# untitled.net
KiCad netlist of a schematic drawn in EAGLE
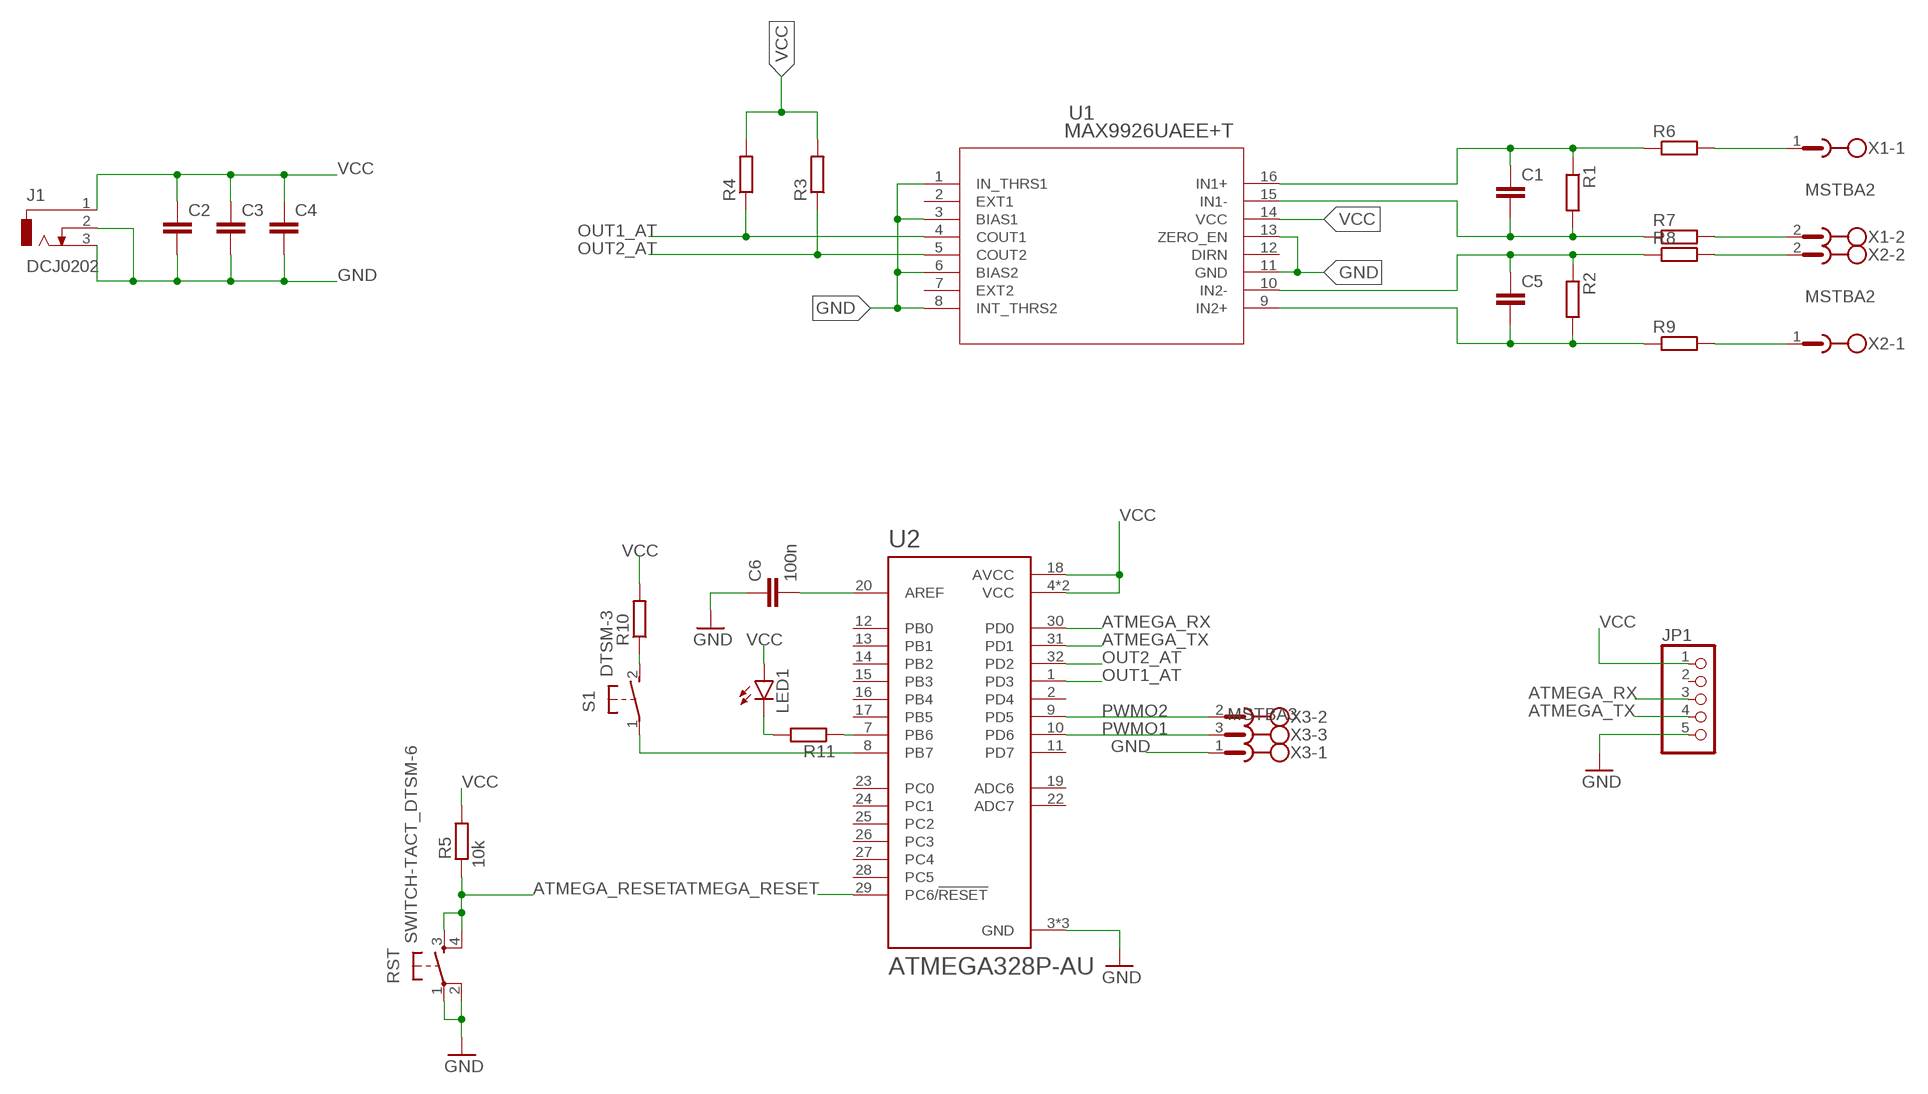
[diagram p0: schematic, sheet 1]

(export (version "E")
  (design (tool "Eeschema 10.0.6"))
  (components
    (comp (ref "C1")
      (value "C-EUC0805")
      (footprint "eagle-import:C0805")
      (libsource (lib "eagle-import") (part "C-EUC0805"))
    )
    (comp (ref "C2")
      (value "C-EUC0805")
      (footprint "eagle-import:C0805")
      (libsource (lib "eagle-import") (part "C-EUC0805"))
    )
    (comp (ref "C3")
      (value "C-EUC0805")
      (footprint "eagle-import:C0805")
      (libsource (lib "eagle-import") (part "C-EUC0805"))
    )
    (comp (ref "C4")
      (value "C-EUC0805")
      (footprint "eagle-import:C0805")
      (libsource (lib "eagle-import") (part "C-EUC0805"))
    )
    (comp (ref "C5")
      (value "C-EUC0805")
      (footprint "eagle-import:C0805")
      (libsource (lib "eagle-import") (part "C-EUC0805"))
    )
    (comp (ref "C6")
      (value "100n")
      (footprint "eagle-import:C0805")
      (libsource (lib "eagle-import") (part "C-EUC0805"))
    )
    (comp (ref "J1")
      (value "DCJ0202")
      (footprint "eagle-import:DCJ0202")
      (libsource (lib "eagle-import") (part "DCJ0202"))
    )
    (comp (ref "JP1")
      (value "PINHD-1X5")
      (footprint "eagle-import:1X05")
      (libsource (lib "eagle-import") (part "PINHD-1X5"))
    )
    (comp (ref "LED1")
      (value "LEDCHIP-LED0805")
      (footprint "eagle-import:CHIP-LED0805")
      (libsource (lib "eagle-import") (part "LEDCHIP-LED0805"))
    )
    (comp (ref "R1")
      (value "R-EU_R1206")
      (footprint "eagle-import:R1206")
      (libsource (lib "eagle-import") (part "R-EU_R1206"))
    )
    (comp (ref "R2")
      (value "R-EU_R1206")
      (footprint "eagle-import:R1206")
      (libsource (lib "eagle-import") (part "R-EU_R1206"))
    )
    (comp (ref "R3")
      (value "R-EU_R1206")
      (footprint "eagle-import:R1206")
      (libsource (lib "eagle-import") (part "R-EU_R1206"))
    )
    (comp (ref "R4")
      (value "R-EU_R1206")
      (footprint "eagle-import:R1206")
      (libsource (lib "eagle-import") (part "R-EU_R1206"))
    )
    (comp (ref "R5")
      (value "10k")
      (footprint "eagle-import:R1206")
      (libsource (lib "eagle-import") (part "R-EU_R1206"))
    )
    (comp (ref "R6")
      (value "R-EU_R2512")
      (footprint "eagle-import:R2512")
      (libsource (lib "eagle-import") (part "R-EU_R2512"))
    )
    (comp (ref "R7")
      (value "R-EU_R2512")
      (footprint "eagle-import:R2512")
      (libsource (lib "eagle-import") (part "R-EU_R2512"))
    )
    (comp (ref "R8")
      (value "R-EU_R2512")
      (footprint "eagle-import:R2512")
      (libsource (lib "eagle-import") (part "R-EU_R2512"))
    )
    (comp (ref "R9")
      (value "R-EU_R2512")
      (footprint "eagle-import:R2512")
      (libsource (lib "eagle-import") (part "R-EU_R2512"))
    )
    (comp (ref "R10")
      (value "R-EU_R1206")
      (footprint "eagle-import:R1206")
      (libsource (lib "eagle-import") (part "R-EU_R1206"))
    )
    (comp (ref "R11")
      (value "R-EU_R1206")
      (footprint "eagle-import:R1206")
      (libsource (lib "eagle-import") (part "R-EU_R1206"))
    )
    (comp (ref "RST")
      (value "SWITCH-TACT_DTSM-6")
      (footprint "eagle-import:SWITCH-TACT_DTSM-6")
      (libsource (lib "eagle-import") (part "SWITCH-TACT_DTSM-6"))
    )
    (comp (ref "S1")
      (value "DTSM-3")
      (footprint "eagle-import:DTSM-3")
      (libsource (lib "eagle-import") (part "DTSM-3"))
    )
    (comp (ref "U1")
      (value "MAX9926UAEE+T")
      (footprint "eagle-import:21-0055H_16_MXM")
      (fields (field (name "COPYRIGHT") "Copyright (C) 2018 Accelerated Designs. All rights reserved"))
      (libsource (lib "eagle-import") (part "MAX9926UAEE+T"))
    )
    (comp (ref "U2")
      (value "ATMEGA328P-AU")
      (footprint "eagle-import:QFP80P900X900X120-32N")
      (fields (field (name "MF") "Microchip Technology"))
      (libsource (lib "eagle-import") (part "ATMEGA328P-AU"))
    )
    (comp (ref "X1")
      (value "MSTBA2")
      (footprint "eagle-import:MSTBA2")
      (fields (field (name "MF") "FARNELL") (field (name "MPN") "1757242"))
      (libsource (lib "eagle-import") (part "MSTBA2"))
    )
    (comp (ref "X2")
      (value "MSTBA2")
      (footprint "eagle-import:MSTBA2")
      (fields (field (name "MF") "FARNELL") (field (name "MPN") "1757242"))
      (libsource (lib "eagle-import") (part "MSTBA2"))
    )
    (comp (ref "X3")
      (value "MSTBA3")
      (footprint "eagle-import:MSTBA3")
      (fields (field (name "MF") "FARNELL") (field (name "MPN") "1757255"))
      (libsource (lib "eagle-import") (part "MSTBA3"))
    )
  )
  (nets
    (net (code "1") (name "/ATMEGA_RESET") (class "Default")
      (node (ref "R5") (pin "1") (pinfunction "1_1") (pintype "passive"))
      (node (ref "RST") (pin "3") (pinfunction "3_3") (pintype "passive"))
      (node (ref "RST") (pin "4") (pinfunction "4_4") (pintype "passive"))
      (node (ref "U2") (pin "29") (pinfunction "PC6/~{RESET}_29") (pintype "bidirectional"))
    )
    (net (code "2") (name "/ATMEGA_RX") (class "Default")
      (node (ref "JP1") (pin "3") (pinfunction "3_3") (pintype "passive"))
      (node (ref "U2") (pin "30") (pinfunction "PD0_30") (pintype "bidirectional"))
    )
    (net (code "3") (name "/ATMEGA_TX") (class "Default")
      (node (ref "JP1") (pin "4") (pinfunction "4_4") (pintype "passive"))
      (node (ref "U2") (pin "31") (pinfunction "PD1_31") (pintype "bidirectional"))
    )
    (net (code "4") (name "/OUT1_AT") (class "Default")
      (node (ref "R4") (pin "1") (pinfunction "1_1") (pintype "passive"))
      (node (ref "U1") (pin "4") (pinfunction "COUT1_4") (pintype "output"))
      (node (ref "U2") (pin "1") (pinfunction "PD3_1") (pintype "bidirectional"))
    )
    (net (code "5") (name "/OUT2_AT") (class "Default")
      (node (ref "R3") (pin "1") (pinfunction "1_1") (pintype "passive"))
      (node (ref "U1") (pin "5") (pinfunction "COUT2_5") (pintype "output"))
      (node (ref "U2") (pin "32") (pinfunction "PD2_32") (pintype "bidirectional"))
    )
    (net (code "6") (name "/PWMO1") (class "Default")
      (node (ref "U2") (pin "10") (pinfunction "PD6_10") (pintype "bidirectional"))
      (node (ref "X3") (pin "3") (pinfunction "1_3") (pintype "passive"))
    )
    (net (code "7") (name "/PWMO2") (class "Default")
      (node (ref "U2") (pin "9") (pinfunction "PD5_9") (pintype "bidirectional"))
      (node (ref "X3") (pin "2") (pinfunction "1_2") (pintype "passive"))
    )
    (net (code "8") (name "GND") (class "Default")
      (node (ref "C2") (pin "2") (pinfunction "2_2") (pintype "passive"))
      (node (ref "C3") (pin "2") (pinfunction "2_2") (pintype "passive"))
      (node (ref "C4") (pin "2") (pinfunction "2_2") (pintype "passive"))
      (node (ref "C6") (pin "1") (pinfunction "1_1") (pintype "passive"))
      (node (ref "J1") (pin "2") (pinfunction "2_2") (pintype "passive"))
      (node (ref "J1") (pin "3") (pinfunction "3_3") (pintype "passive"))
      (node (ref "JP1") (pin "5") (pinfunction "5_5") (pintype "passive"))
      (node (ref "RST") (pin "1") (pinfunction "1_1") (pintype "passive"))
      (node (ref "RST") (pin "2") (pinfunction "2_2") (pintype "passive"))
      (node (ref "U1") (pin "1") (pinfunction "IN_THRS1_1") (pintype "passive"))
      (node (ref "U1") (pin "11") (pinfunction "GND_11") (pintype "passive"))
      (node (ref "U1") (pin "13") (pinfunction "ZERO_EN_13") (pintype "passive"))
      (node (ref "U1") (pin "3") (pinfunction "BIAS1_3") (pintype "bidirectional"))
      (node (ref "U1") (pin "6") (pinfunction "BIAS2_6") (pintype "bidirectional"))
      (node (ref "U1") (pin "8") (pinfunction "INT_THRS2_8") (pintype "passive"))
      (node (ref "U2") (pin "21") (pinfunction "GND_21") (pintype "power_in"))
      (node (ref "U2") (pin "3") (pinfunction "GND_3") (pintype "power_in"))
      (node (ref "U2") (pin "5") (pinfunction "GND_5") (pintype "power_in"))
      (node (ref "X3") (pin "1") (pinfunction "1_1") (pintype "passive"))
    )
    (net (code "9") (name "Net-(LED1-PadC)") (class "Default")
      (node (ref "LED1") (pin "C") (pinfunction "C_C") (pintype "passive"))
      (node (ref "R11") (pin "2") (pinfunction "2_2") (pintype "passive"))
    )
    (net (code "10") (name "Net-(R6-Pad2)") (class "Default")
      (node (ref "R6") (pin "2") (pinfunction "2_2") (pintype "passive"))
      (node (ref "X1") (pin "1") (pinfunction "1_1") (pintype "passive"))
    )
    (net (code "11") (name "Net-(R9-Pad2)") (class "Default")
      (node (ref "R9") (pin "2") (pinfunction "2_2") (pintype "passive"))
      (node (ref "X2") (pin "1") (pinfunction "1_1") (pintype "passive"))
    )
    (net (code "12") (name "Net-(R10-Pad1)") (class "Default")
      (node (ref "R10") (pin "1") (pinfunction "1_1") (pintype "passive"))
      (node (ref "S1") (pin "2") (pinfunction "2_2") (pintype "passive"))
    )
    (net (code "13") (name "Net-(U1-IN1+)") (class "Default")
      (node (ref "C1") (pin "1") (pinfunction "1_1") (pintype "passive"))
      (node (ref "R1") (pin "1") (pinfunction "1_1") (pintype "passive"))
      (node (ref "R6") (pin "1") (pinfunction "1_1") (pintype "passive"))
      (node (ref "U1") (pin "16") (pinfunction "IN1+_16") (pintype "input"))
    )
    (net (code "14") (name "Net-(U1-IN1-)") (class "Default")
      (node (ref "C1") (pin "2") (pinfunction "2_2") (pintype "passive"))
      (node (ref "R1") (pin "2") (pinfunction "2_2") (pintype "passive"))
      (node (ref "R7") (pin "1") (pinfunction "1_1") (pintype "passive"))
      (node (ref "U1") (pin "15") (pinfunction "IN1-_15") (pintype "input"))
    )
    (net (code "15") (name "Net-(U1-IN2+)") (class "Default")
      (node (ref "C5") (pin "2") (pinfunction "2_2") (pintype "passive"))
      (node (ref "R2") (pin "2") (pinfunction "2_2") (pintype "passive"))
      (node (ref "R9") (pin "1") (pinfunction "1_1") (pintype "passive"))
      (node (ref "U1") (pin "9") (pinfunction "IN2+_9") (pintype "input"))
    )
    (net (code "16") (name "Net-(U1-IN2-)") (class "Default")
      (node (ref "C5") (pin "1") (pinfunction "1_1") (pintype "passive"))
      (node (ref "R2") (pin "1") (pinfunction "1_1") (pintype "passive"))
      (node (ref "R8") (pin "1") (pinfunction "1_1") (pintype "passive"))
      (node (ref "U1") (pin "10") (pinfunction "IN2-_10") (pintype "input"))
    )
    (net (code "17") (name "Net-(U2-AREF)") (class "Default")
      (node (ref "C6") (pin "2") (pinfunction "2_2") (pintype "passive"))
      (node (ref "U2") (pin "20") (pinfunction "AREF_20") (pintype "input"))
    )
    (net (code "18") (name "Net-(U2-PB6)") (class "Default")
      (node (ref "R11") (pin "1") (pinfunction "1_1") (pintype "passive"))
      (node (ref "U2") (pin "7") (pinfunction "PB6_7") (pintype "bidirectional"))
    )
    (net (code "19") (name "Net-(U2-PB7)") (class "Default")
      (node (ref "S1") (pin "1") (pinfunction "1_1") (pintype "passive"))
      (node (ref "U2") (pin "8") (pinfunction "PB7_8") (pintype "bidirectional"))
    )
    (net (code "20") (name "Net-(X1B-1)") (class "Default")
      (node (ref "R7") (pin "2") (pinfunction "2_2") (pintype "passive"))
      (node (ref "X1") (pin "2") (pinfunction "1_2") (pintype "passive"))
    )
    (net (code "21") (name "Net-(X2B-1)") (class "Default")
      (node (ref "R8") (pin "2") (pinfunction "2_2") (pintype "passive"))
      (node (ref "X2") (pin "2") (pinfunction "1_2") (pintype "passive"))
    )
    (net (code "22") (name "VCC") (class "Default")
      (node (ref "C2") (pin "1") (pinfunction "1_1") (pintype "passive"))
      (node (ref "C3") (pin "1") (pinfunction "1_1") (pintype "passive"))
      (node (ref "C4") (pin "1") (pinfunction "1_1") (pintype "passive"))
      (node (ref "J1") (pin "1") (pinfunction "1_1") (pintype "passive"))
      (node (ref "JP1") (pin "1") (pinfunction "1_1") (pintype "passive"))
      (node (ref "LED1") (pin "A") (pinfunction "A_A") (pintype "passive"))
      (node (ref "R10") (pin "2") (pinfunction "2_2") (pintype "passive"))
      (node (ref "R3") (pin "2") (pinfunction "2_2") (pintype "passive"))
      (node (ref "R4") (pin "2") (pinfunction "2_2") (pintype "passive"))
      (node (ref "R5") (pin "2") (pinfunction "2_2") (pintype "passive"))
      (node (ref "U1") (pin "14") (pinfunction "VCC_14") (pintype "power_in"))
      (node (ref "U2") (pin "18") (pinfunction "AVCC_18") (pintype "power_in"))
      (node (ref "U2") (pin "4") (pinfunction "VCC_4") (pintype "power_in"))
      (node (ref "U2") (pin "6") (pinfunction "VCC_6") (pintype "power_in"))
    )
    (net (code "23") (name "unconnected-(JP1-Pad2)") (class "Default")
      (node (ref "JP1") (pin "2") (pinfunction "2_2") (pintype "passive"))
    )
    (net (code "24") (name "unconnected-(U1-DIRN-Pad12)") (class "Default")
      (node (ref "U1") (pin "12") (pinfunction "DIRN_12") (pintype "passive"))
    )
    (net (code "25") (name "unconnected-(U1-EXT1-Pad2)") (class "Default")
      (node (ref "U1") (pin "2") (pinfunction "EXT1_2") (pintype "bidirectional"))
    )
    (net (code "26") (name "unconnected-(U1-EXT2-Pad7)") (class "Default")
      (node (ref "U1") (pin "7") (pinfunction "EXT2_7") (pintype "bidirectional"))
    )
    (net (code "27") (name "unconnected-(U2-ADC6-Pad19)") (class "Default")
      (node (ref "U2") (pin "19") (pinfunction "ADC6_19") (pintype "bidirectional"))
    )
    (net (code "28") (name "unconnected-(U2-ADC7-Pad22)") (class "Default")
      (node (ref "U2") (pin "22") (pinfunction "ADC7_22") (pintype "bidirectional"))
    )
    (net (code "29") (name "unconnected-(U2-PB0-Pad12)") (class "Default")
      (node (ref "U2") (pin "12") (pinfunction "PB0_12") (pintype "bidirectional"))
    )
    (net (code "30") (name "unconnected-(U2-PB1-Pad13)") (class "Default")
      (node (ref "U2") (pin "13") (pinfunction "PB1_13") (pintype "bidirectional"))
    )
    (net (code "31") (name "unconnected-(U2-PB2-Pad14)") (class "Default")
      (node (ref "U2") (pin "14") (pinfunction "PB2_14") (pintype "bidirectional"))
    )
    (net (code "32") (name "unconnected-(U2-PB3-Pad15)") (class "Default")
      (node (ref "U2") (pin "15") (pinfunction "PB3_15") (pintype "bidirectional"))
    )
    (net (code "33") (name "unconnected-(U2-PB4-Pad16)") (class "Default")
      (node (ref "U2") (pin "16") (pinfunction "PB4_16") (pintype "bidirectional"))
    )
    (net (code "34") (name "unconnected-(U2-PB5-Pad17)") (class "Default")
      (node (ref "U2") (pin "17") (pinfunction "PB5_17") (pintype "bidirectional"))
    )
    (net (code "35") (name "unconnected-(U2-PC0-Pad23)") (class "Default")
      (node (ref "U2") (pin "23") (pinfunction "PC0_23") (pintype "bidirectional"))
    )
    (net (code "36") (name "unconnected-(U2-PC1-Pad24)") (class "Default")
      (node (ref "U2") (pin "24") (pinfunction "PC1_24") (pintype "bidirectional"))
    )
    (net (code "37") (name "unconnected-(U2-PC2-Pad25)") (class "Default")
      (node (ref "U2") (pin "25") (pinfunction "PC2_25") (pintype "bidirectional"))
    )
    (net (code "38") (name "unconnected-(U2-PC3-Pad26)") (class "Default")
      (node (ref "U2") (pin "26") (pinfunction "PC3_26") (pintype "bidirectional"))
    )
    (net (code "39") (name "unconnected-(U2-PC4-Pad27)") (class "Default")
      (node (ref "U2") (pin "27") (pinfunction "PC4_27") (pintype "bidirectional"))
    )
    (net (code "40") (name "unconnected-(U2-PC5-Pad28)") (class "Default")
      (node (ref "U2") (pin "28") (pinfunction "PC5_28") (pintype "bidirectional"))
    )
    (net (code "41") (name "unconnected-(U2-PD4-Pad2)") (class "Default")
      (node (ref "U2") (pin "2") (pinfunction "PD4_2") (pintype "bidirectional"))
    )
    (net (code "42") (name "unconnected-(U2-PD7-Pad11)") (class "Default")
      (node (ref "U2") (pin "11") (pinfunction "PD7_11") (pintype "bidirectional"))
    )
  )
)
